# design.net
KiCad netlist of a schematic drawn in Altium Designer
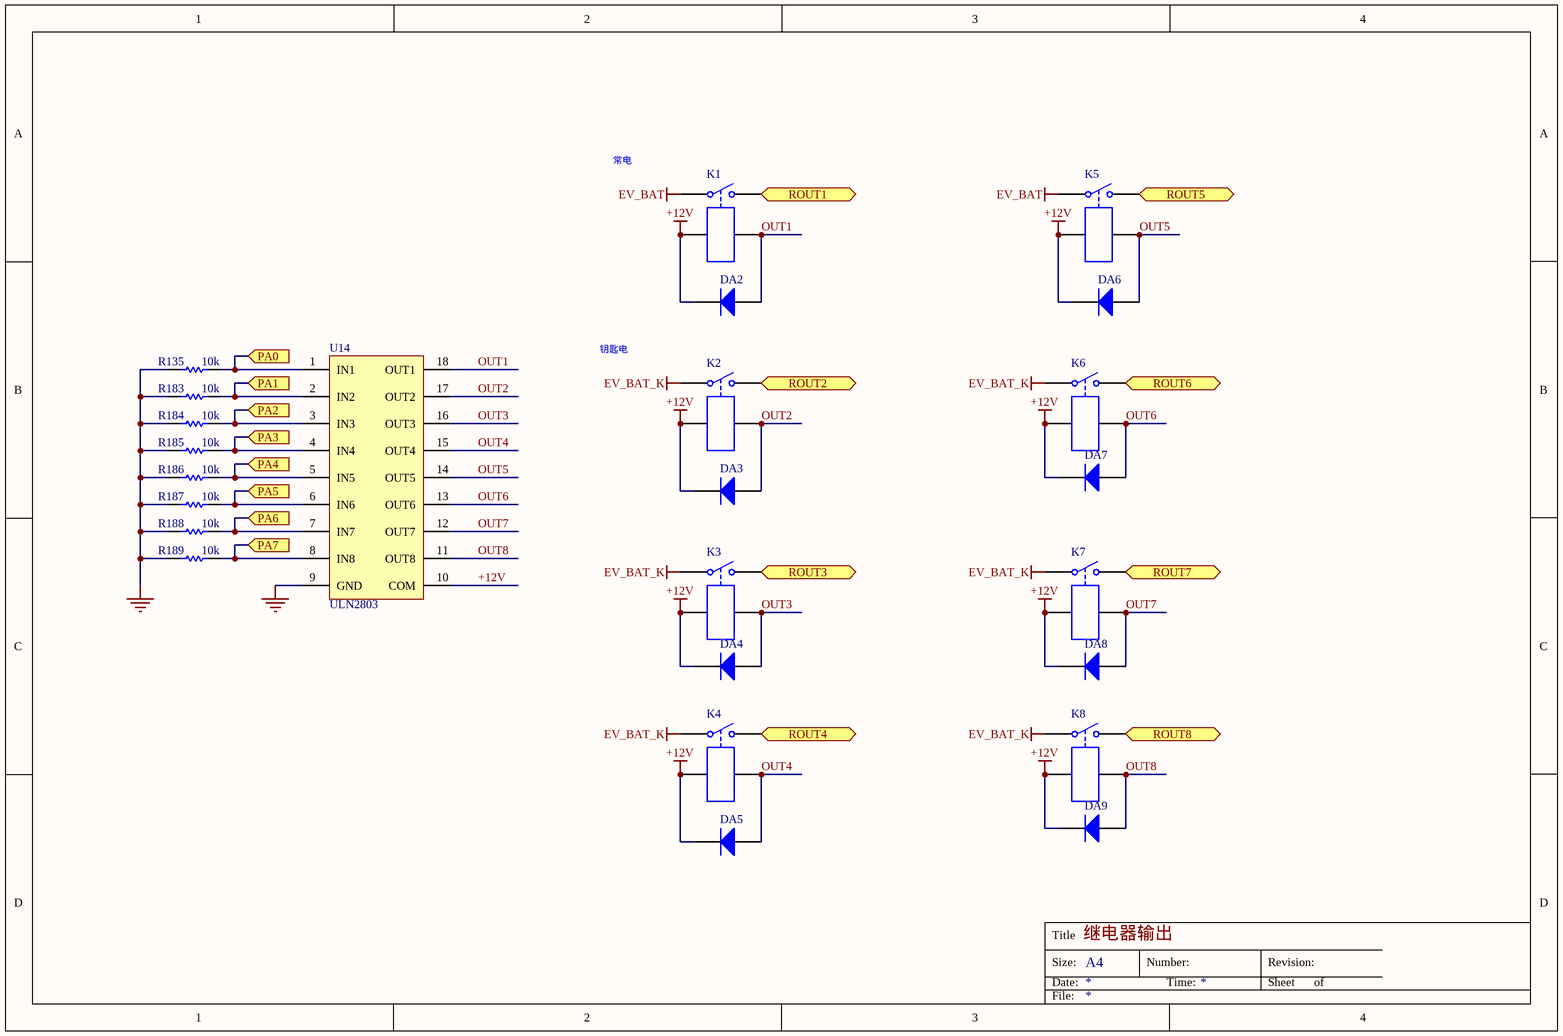
[diagram p0: 继电器功率驱动输出.SchDoc]

(export (version "E")
  (design (tool "Eeschema 10.0.6"))
  (components
    (comp (ref "DA2")
      (value "Diode 1N4148")
      (footprint "SMB")
      (description "High Conductance Fast Diode")
      (fields (field (name "PUBLISHER") "Altium Limited"))
      (libsource (lib "Miscellaneous Devices") (part "Diode 1N4148"))
    )
    (comp (ref "DA3")
      (value "Diode 1N4148")
      (footprint "SMB")
      (description "High Conductance Fast Diode")
      (fields (field (name "PUBLISHER") "Altium Limited"))
      (libsource (lib "Miscellaneous Devices") (part "Diode 1N4148"))
    )
    (comp (ref "DA4")
      (value "Diode 1N4148")
      (footprint "SMB")
      (description "High Conductance Fast Diode")
      (fields (field (name "PUBLISHER") "Altium Limited"))
      (libsource (lib "Miscellaneous Devices") (part "Diode 1N4148"))
    )
    (comp (ref "DA5")
      (value "Diode 1N4148")
      (footprint "SMB")
      (description "High Conductance Fast Diode")
      (fields (field (name "PUBLISHER") "Altium Limited"))
      (libsource (lib "Miscellaneous Devices") (part "Diode 1N4148"))
    )
    (comp (ref "DA6")
      (value "Diode 1N4148")
      (footprint "SMB")
      (description "High Conductance Fast Diode")
      (fields (field (name "PUBLISHER") "Altium Limited"))
      (libsource (lib "Miscellaneous Devices") (part "Diode 1N4148"))
    )
    (comp (ref "DA7")
      (value "Diode 1N4148")
      (footprint "SMB")
      (description "High Conductance Fast Diode")
      (fields (field (name "PUBLISHER") "Altium Limited"))
      (libsource (lib "Miscellaneous Devices") (part "Diode 1N4148"))
    )
    (comp (ref "DA8")
      (value "Diode 1N4148")
      (footprint "SMB")
      (description "High Conductance Fast Diode")
      (fields (field (name "PUBLISHER") "Altium Limited"))
      (libsource (lib "Miscellaneous Devices") (part "Diode 1N4148"))
    )
    (comp (ref "DA9")
      (value "Diode 1N4148")
      (footprint "SMB")
      (description "High Conductance Fast Diode")
      (fields (field (name "PUBLISHER") "Altium Limited"))
      (libsource (lib "Miscellaneous Devices") (part "Diode 1N4148"))
    )
    (comp (ref "K1")
      (value "Relay-SPST")
      (footprint "继电器宏发")
      (description "Single-Pole Single-Throw Relay")
      (fields (field (name "PUBLISHER") "Altium Limited"))
      (libsource (lib "Miscellaneous Devices") (part "Relay-SPST"))
    )
    (comp (ref "K2")
      (value "Relay-SPST")
      (footprint "继电器宏发")
      (description "Single-Pole Single-Throw Relay")
      (fields (field (name "PUBLISHER") "Altium Limited"))
      (libsource (lib "Miscellaneous Devices") (part "Relay-SPST"))
    )
    (comp (ref "K3")
      (value "Relay-SPST")
      (footprint "整车控制器封装 全:继电器宏发")
      (description "Single-Pole Single-Throw Relay")
      (fields (field (name "PUBLISHER") "Altium Limited"))
      (libsource (lib "Miscellaneous Devices") (part "Relay-SPST"))
    )
    (comp (ref "K4")
      (value "Relay-SPST")
      (footprint "继电器宏发")
      (description "Single-Pole Single-Throw Relay")
      (fields (field (name "PUBLISHER") "Altium Limited"))
      (libsource (lib "Miscellaneous Devices") (part "Relay-SPST"))
    )
    (comp (ref "K5")
      (value "Relay-SPST")
      (footprint "继电器宏发")
      (description "Single-Pole Single-Throw Relay")
      (fields (field (name "PUBLISHER") "Altium Limited"))
      (libsource (lib "Miscellaneous Devices") (part "Relay-SPST"))
    )
    (comp (ref "K6")
      (value "Relay-SPST")
      (footprint "继电器宏发")
      (description "Single-Pole Single-Throw Relay")
      (fields (field (name "PUBLISHER") "Altium Limited"))
      (libsource (lib "Miscellaneous Devices") (part "Relay-SPST"))
    )
    (comp (ref "K7")
      (value "Relay-SPST")
      (footprint "继电器宏发")
      (description "Single-Pole Single-Throw Relay")
      (fields (field (name "PUBLISHER") "Altium Limited"))
      (libsource (lib "Miscellaneous Devices") (part "Relay-SPST"))
    )
    (comp (ref "K8")
      (value "Relay-SPST")
      (footprint "继电器宏发")
      (description "Single-Pole Single-Throw Relay")
      (fields (field (name "PUBLISHER") "Altium Limited"))
      (libsource (lib "Miscellaneous Devices") (part "Relay-SPST"))
    )
    (comp (ref "R135")
      (value "10k")
      (footprint "0603-Resistor")
      (description "RES, 10k ohm, 0.1%, 0.1W, 0603")
      (fields
        (field (name "MANUFACTURER") "YAGEO")
        (field (name "PARTNUMBER") "RT0603BRD0710KL")
        (field (name "PUBLISHER") "YAGEO")
      )
      (libsource (lib "Resistor") (part "RT0603BRD0710KL"))
    )
    (comp (ref "R183")
      (value "10k")
      (footprint "0603-Resistor")
      (description "RES, 10k ohm, 0.1%, 0.1W, 0603")
      (fields
        (field (name "MANUFACTURER") "YAGEO")
        (field (name "PARTNUMBER") "RT0603BRD0710KL")
        (field (name "PUBLISHER") "YAGEO")
      )
      (libsource (lib "Resistor") (part "RT0603BRD0710KL"))
    )
    (comp (ref "R184")
      (value "10k")
      (footprint "0603-Resistor")
      (description "RES, 10k ohm, 0.1%, 0.1W, 0603")
      (fields
        (field (name "MANUFACTURER") "YAGEO")
        (field (name "PARTNUMBER") "RT0603BRD0710KL")
        (field (name "PUBLISHER") "YAGEO")
      )
      (libsource (lib "Resistor") (part "RT0603BRD0710KL"))
    )
    (comp (ref "R185")
      (value "10k")
      (footprint "0603-Resistor")
      (description "RES, 10k ohm, 0.1%, 0.1W, 0603")
      (fields
        (field (name "MANUFACTURER") "YAGEO")
        (field (name "PARTNUMBER") "RT0603BRD0710KL")
        (field (name "PUBLISHER") "YAGEO")
      )
      (libsource (lib "Resistor") (part "RT0603BRD0710KL"))
    )
    (comp (ref "R186")
      (value "10k")
      (footprint "0603-Resistor")
      (description "RES, 10k ohm, 0.1%, 0.1W, 0603")
      (fields
        (field (name "MANUFACTURER") "YAGEO")
        (field (name "PARTNUMBER") "RT0603BRD0710KL")
        (field (name "PUBLISHER") "YAGEO")
      )
      (libsource (lib "Resistor") (part "RT0603BRD0710KL"))
    )
    (comp (ref "R187")
      (value "10k")
      (footprint "0603-Resistor")
      (description "RES, 10k ohm, 0.1%, 0.1W, 0603")
      (fields
        (field (name "MANUFACTURER") "YAGEO")
        (field (name "PARTNUMBER") "RT0603BRD0710KL")
        (field (name "PUBLISHER") "YAGEO")
      )
      (libsource (lib "Resistor") (part "RT0603BRD0710KL"))
    )
    (comp (ref "R188")
      (value "10k")
      (footprint "0603-Resistor")
      (description "RES, 10k ohm, 0.1%, 0.1W, 0603")
      (fields
        (field (name "MANUFACTURER") "YAGEO")
        (field (name "PARTNUMBER") "RT0603BRD0710KL")
        (field (name "PUBLISHER") "YAGEO")
      )
      (libsource (lib "Resistor") (part "RT0603BRD0710KL"))
    )
    (comp (ref "R189")
      (value "10k")
      (footprint "0603-Resistor")
      (description "RES, 10k ohm, 0.1%, 0.1W, 0603")
      (fields
        (field (name "MANUFACTURER") "YAGEO")
        (field (name "PARTNUMBER") "RT0603BRD0710KL")
        (field (name "PUBLISHER") "YAGEO")
      )
      (libsource (lib "Resistor") (part "RT0603BRD0710KL"))
    )
    (comp (ref "U14") (value "ULN2803") (footprint "VCU:U14") (libsource (lib "BMS") (part "ULN2803")))
  )
  (nets
    (net (code "1") (name "+12V") (class "Default")
      (node (ref "DA2") (pin "2") (pinfunction "K_2") (pintype "passive"))
      (node (ref "DA3") (pin "2") (pinfunction "K_2") (pintype "passive"))
      (node (ref "DA4") (pin "2") (pinfunction "K_2") (pintype "passive"))
      (node (ref "DA5") (pin "2") (pinfunction "K_2") (pintype "passive"))
      (node (ref "DA6") (pin "2") (pinfunction "K_2") (pintype "passive"))
      (node (ref "DA7") (pin "2") (pinfunction "K_2") (pintype "passive"))
      (node (ref "DA8") (pin "2") (pinfunction "K_2") (pintype "passive"))
      (node (ref "DA9") (pin "2") (pinfunction "K_2") (pintype "passive"))
      (node (ref "K1") (pin "3") (pinfunction "3_3") (pintype "passive"))
      (node (ref "K2") (pin "3") (pinfunction "3_3") (pintype "passive"))
      (node (ref "K3") (pin "3") (pinfunction "3_3") (pintype "passive"))
      (node (ref "K4") (pin "3") (pinfunction "3_3") (pintype "passive"))
      (node (ref "K5") (pin "3") (pinfunction "3_3") (pintype "passive"))
      (node (ref "K6") (pin "3") (pinfunction "3_3") (pintype "passive"))
      (node (ref "K7") (pin "3") (pinfunction "3_3") (pintype "passive"))
      (node (ref "K8") (pin "3") (pinfunction "3_3") (pintype "passive"))
      (node (ref "U14") (pin "10") (pinfunction "COM_10") (pintype "passive"))
    )
    (net (code "2") (name "/OUT1") (class "Default")
      (node (ref "DA2") (pin "1") (pinfunction "A_1") (pintype "passive"))
      (node (ref "K1") (pin "4") (pinfunction "4_4") (pintype "passive"))
      (node (ref "U14") (pin "18") (pinfunction "OUT1_18") (pintype "passive"))
    )
    (net (code "3") (name "/OUT2") (class "Default")
      (node (ref "DA3") (pin "1") (pinfunction "A_1") (pintype "passive"))
      (node (ref "K2") (pin "4") (pinfunction "4_4") (pintype "passive"))
      (node (ref "U14") (pin "17") (pinfunction "OUT2_17") (pintype "passive"))
    )
    (net (code "4") (name "/OUT3") (class "Default")
      (node (ref "DA4") (pin "1") (pinfunction "A_1") (pintype "passive"))
      (node (ref "K3") (pin "4") (pinfunction "4_4") (pintype "passive"))
      (node (ref "U14") (pin "16") (pinfunction "OUT3_16") (pintype "passive"))
    )
    (net (code "5") (name "/OUT4") (class "Default")
      (node (ref "DA5") (pin "1") (pinfunction "A_1") (pintype "passive"))
      (node (ref "K4") (pin "4") (pinfunction "4_4") (pintype "passive"))
      (node (ref "U14") (pin "15") (pinfunction "OUT4_15") (pintype "passive"))
    )
    (net (code "6") (name "/OUT5") (class "Default")
      (node (ref "DA6") (pin "1") (pinfunction "A_1") (pintype "passive"))
      (node (ref "K5") (pin "4") (pinfunction "4_4") (pintype "passive"))
      (node (ref "U14") (pin "14") (pinfunction "OUT5_14") (pintype "passive"))
    )
    (net (code "7") (name "/OUT6") (class "Default")
      (node (ref "DA7") (pin "1") (pinfunction "A_1") (pintype "passive"))
      (node (ref "K6") (pin "4") (pinfunction "4_4") (pintype "passive"))
      (node (ref "U14") (pin "13") (pinfunction "OUT6_13") (pintype "passive"))
    )
    (net (code "8") (name "/OUT7") (class "Default")
      (node (ref "DA8") (pin "1") (pinfunction "A_1") (pintype "passive"))
      (node (ref "K7") (pin "4") (pinfunction "4_4") (pintype "passive"))
      (node (ref "U14") (pin "12") (pinfunction "OUT7_12") (pintype "passive"))
    )
    (net (code "9") (name "/OUT8") (class "Default")
      (node (ref "DA9") (pin "1") (pinfunction "A_1") (pintype "passive"))
      (node (ref "K8") (pin "4") (pinfunction "4_4") (pintype "passive"))
      (node (ref "U14") (pin "11") (pinfunction "OUT8_11") (pintype "passive"))
    )
    (net (code "10") (name "/PA0") (class "Default")
      (node (ref "R135") (pin "2") (pinfunction "2_2") (pintype "passive"))
      (node (ref "U14") (pin "1") (pinfunction "IN1_1") (pintype "passive"))
    )
    (net (code "11") (name "/PA1") (class "Default")
      (node (ref "R183") (pin "2") (pinfunction "2_2") (pintype "passive"))
      (node (ref "U14") (pin "2") (pinfunction "IN2_2") (pintype "passive"))
    )
    (net (code "12") (name "/PA2") (class "Default")
      (node (ref "R184") (pin "2") (pinfunction "2_2") (pintype "passive"))
      (node (ref "U14") (pin "3") (pinfunction "IN3_3") (pintype "passive"))
    )
    (net (code "13") (name "/PA3") (class "Default")
      (node (ref "R185") (pin "2") (pinfunction "2_2") (pintype "passive"))
      (node (ref "U14") (pin "4") (pinfunction "IN4_4") (pintype "passive"))
    )
    (net (code "14") (name "/PA4") (class "Default")
      (node (ref "R186") (pin "2") (pinfunction "2_2") (pintype "passive"))
      (node (ref "U14") (pin "5") (pinfunction "IN5_5") (pintype "passive"))
    )
    (net (code "15") (name "/PA5") (class "Default")
      (node (ref "R187") (pin "2") (pinfunction "2_2") (pintype "passive"))
      (node (ref "U14") (pin "6") (pinfunction "IN6_6") (pintype "passive"))
    )
    (net (code "16") (name "/PA6") (class "Default")
      (node (ref "R188") (pin "2") (pinfunction "2_2") (pintype "passive"))
      (node (ref "U14") (pin "7") (pinfunction "IN7_7") (pintype "passive"))
    )
    (net (code "17") (name "/PA7") (class "Default")
      (node (ref "R189") (pin "2") (pinfunction "2_2") (pintype "passive"))
      (node (ref "U14") (pin "8") (pinfunction "IN8_8") (pintype "passive"))
    )
    (net (code "18") (name "/ROUT1") (class "Default")
      (node (ref "K1") (pin "2") (pinfunction "2_2") (pintype "passive"))
    )
    (net (code "19") (name "/ROUT2") (class "Default")
      (node (ref "K2") (pin "2") (pinfunction "2_2") (pintype "passive"))
    )
    (net (code "20") (name "/ROUT3") (class "Default")
      (node (ref "K3") (pin "2") (pinfunction "2_2") (pintype "passive"))
    )
    (net (code "21") (name "/ROUT4") (class "Default")
      (node (ref "K4") (pin "2") (pinfunction "2_2") (pintype "passive"))
    )
    (net (code "22") (name "/ROUT5") (class "Default")
      (node (ref "K5") (pin "2") (pinfunction "2_2") (pintype "passive"))
    )
    (net (code "23") (name "/ROUT6") (class "Default")
      (node (ref "K6") (pin "2") (pinfunction "2_2") (pintype "passive"))
    )
    (net (code "24") (name "/ROUT7") (class "Default")
      (node (ref "K7") (pin "2") (pinfunction "2_2") (pintype "passive"))
    )
    (net (code "25") (name "/ROUT8") (class "Default")
      (node (ref "K8") (pin "2") (pinfunction "2_2") (pintype "passive"))
    )
    (net (code "26") (name "EV_BAT") (class "Default")
      (node (ref "K1") (pin "1") (pinfunction "1_1") (pintype "passive"))
      (node (ref "K5") (pin "1") (pinfunction "1_1") (pintype "passive"))
    )
    (net (code "27") (name "EV_BAT_K") (class "Default")
      (node (ref "K2") (pin "1") (pinfunction "1_1") (pintype "passive"))
      (node (ref "K3") (pin "1") (pinfunction "1_1") (pintype "passive"))
      (node (ref "K4") (pin "1") (pinfunction "1_1") (pintype "passive"))
      (node (ref "K6") (pin "1") (pinfunction "1_1") (pintype "passive"))
      (node (ref "K7") (pin "1") (pinfunction "1_1") (pintype "passive"))
      (node (ref "K8") (pin "1") (pinfunction "1_1") (pintype "passive"))
    )
    (net (code "28") (name "GND") (class "Default")
      (node (ref "R135") (pin "1") (pinfunction "1_1") (pintype "passive"))
      (node (ref "R183") (pin "1") (pinfunction "1_1") (pintype "passive"))
      (node (ref "R184") (pin "1") (pinfunction "1_1") (pintype "passive"))
      (node (ref "R185") (pin "1") (pinfunction "1_1") (pintype "passive"))
      (node (ref "R186") (pin "1") (pinfunction "1_1") (pintype "passive"))
      (node (ref "R187") (pin "1") (pinfunction "1_1") (pintype "passive"))
      (node (ref "R188") (pin "1") (pinfunction "1_1") (pintype "passive"))
      (node (ref "R189") (pin "1") (pinfunction "1_1") (pintype "passive"))
      (node (ref "U14") (pin "9") (pinfunction "GND_9") (pintype "passive"))
    )
  )
)
